# Relay_Outputs.net
KiCad netlist of a schematic drawn in Altium Designer
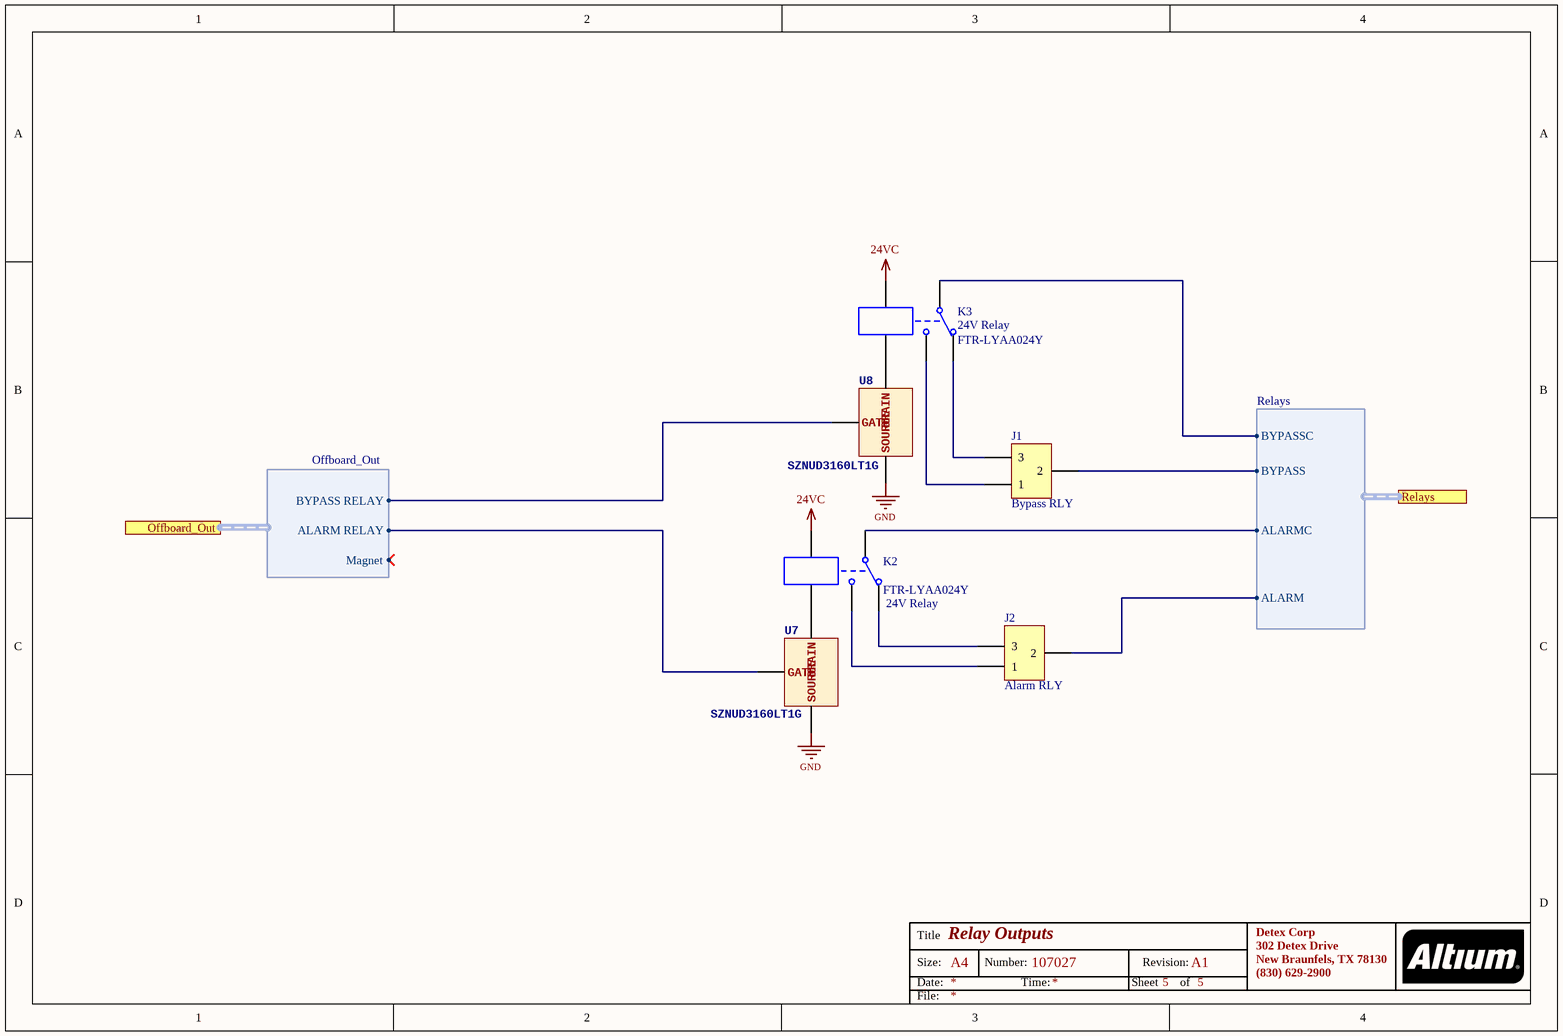
[diagram p0: Relay_Outputs.SchDoc]

(export (version "E")
  (design (tool "Eeschema 10.0.6"))
  (components
    (comp (ref "J1")
      (value "Bypass RLY")
      (footprint "3 Pin Header for Relay")
      (description "Header, 3-Pin")
      (libsource (lib "") (part "Header 3_1"))
    )
    (comp (ref "J2")
      (value "Alarm RLY")
      (footprint "3 Pin Header for Relay")
      (description "Header, 3-Pin")
      (libsource (lib "Custom Components") (part "Header 3"))
    )
    (comp (ref "K2")
      (value "24V Relay")
      (footprint "FTR-LY")
      (description "SPST (1 Form A)")
      (fields (field (name "MFR") "Fujitsu") (field (name "MFR P/N") "FTR-LYAA024Y"))
      (libsource (lib "Miscellaneous Devices") (part "Relay-SPDT"))
    )
    (comp (ref "K3")
      (value "24V Relay")
      (footprint "FTR-LY")
      (description "SPST (1 Form A)")
      (fields (field (name "MFR") "Fujitsu") (field (name "MFR P/N") "FTR-LYAA024Y"))
      (libsource (lib "Miscellaneous Devices") (part "Relay-SPDT"))
    )
    (comp (ref "U7")
      (value "SZNUD3160LT1G")
      (footprint "SOT-23_N")
      (fields (field (name "MFR") "ON Semiconductor"))
      (libsource (lib "Custom Components") (part "SZNUD3160LT1G"))
    )
    (comp (ref "U8")
      (value "SZNUD3160LT1G")
      (footprint "SOT-23_N")
      (fields (field (name "MFR") "ON Semiconductor"))
      (libsource (lib "Custom Components") (part "SZNUD3160LT1G"))
    )
  )
  (nets
    (net (code "3") (name "/ALARM") (class "Default")
      (node (ref "J2") (pin "2") (pinfunction "2_2") (pintype "passive"))
    )
    (net (code "4") (name "/ALARM RELAY") (class "Default")
      (node (ref "U7") (pin "1") (pinfunction "GATE_1") (pintype "passive"))
    )
    (net (code "5") (name "/ALARMC") (class "Default")
      (node (ref "K2") (pin "1") (pinfunction "COM_1") (pintype "passive"))
    )
    (net (code "6") (name "/BYPASS") (class "Default")
      (node (ref "J1") (pin "2") (pinfunction "2_2") (pintype "passive"))
    )
    (net (code "7") (name "/BYPASS RELAY") (class "Default")
      (node (ref "U8") (pin "1") (pinfunction "GATE_1") (pintype "passive"))
    )
    (net (code "8") (name "/BYPASSC") (class "Default")
      (node (ref "K3") (pin "1") (pinfunction "COM_1") (pintype "passive"))
    )
    (net (code "11") (name "24VC") (class "Default")
      (node (ref "K2") (pin "4") (pinfunction "4_4") (pintype "passive"))
      (node (ref "K3") (pin "4") (pinfunction "4_4") (pintype "passive"))
    )
    (net (code "12") (name "GND") (class "Default")
      (node (ref "U7") (pin "2") (pinfunction "SOURCE_2") (pintype "passive"))
      (node (ref "U8") (pin "2") (pinfunction "SOURCE_2") (pintype "passive"))
    )
    (net (code "13") (name "Net-(K2-N{slash}C)") (class "Default")
      (node (ref "J2") (pin "3") (pinfunction "3_3") (pintype "passive"))
      (node (ref "K2") (pin "2") (pinfunction "N/C_2") (pintype "passive"))
    )
    (net (code "14") (name "Net-(K2-N{slash}O)") (class "Default")
      (node (ref "J2") (pin "1") (pinfunction "1_1") (pintype "passive"))
      (node (ref "K2") (pin "3") (pinfunction "N/O_3") (pintype "passive"))
    )
    (net (code "15") (name "Net-(K3-N{slash}C)") (class "Default")
      (node (ref "J1") (pin "3") (pinfunction "3_3") (pintype "passive"))
      (node (ref "K3") (pin "2") (pinfunction "N/C_2") (pintype "passive"))
    )
    (net (code "16") (name "Net-(K3-N{slash}O)") (class "Default")
      (node (ref "J1") (pin "1") (pinfunction "1_1") (pintype "passive"))
      (node (ref "K3") (pin "3") (pinfunction "N/O_3") (pintype "passive"))
    )
    (net (code "17") (name "Net-(U7-DRAIN)") (class "Default")
      (node (ref "K2") (pin "5") (pinfunction "5_5") (pintype "passive"))
      (node (ref "U7") (pin "3") (pinfunction "DRAIN_3") (pintype "passive"))
    )
    (net (code "18") (name "Net-(U8-DRAIN)") (class "Default")
      (node (ref "K3") (pin "5") (pinfunction "5_5") (pintype "passive"))
      (node (ref "U8") (pin "3") (pinfunction "DRAIN_3") (pintype "passive"))
    )
  )
)
